# devboard_kw2xd_v2_0.net
KiCad netlist of a schematic drawn in EAGLE
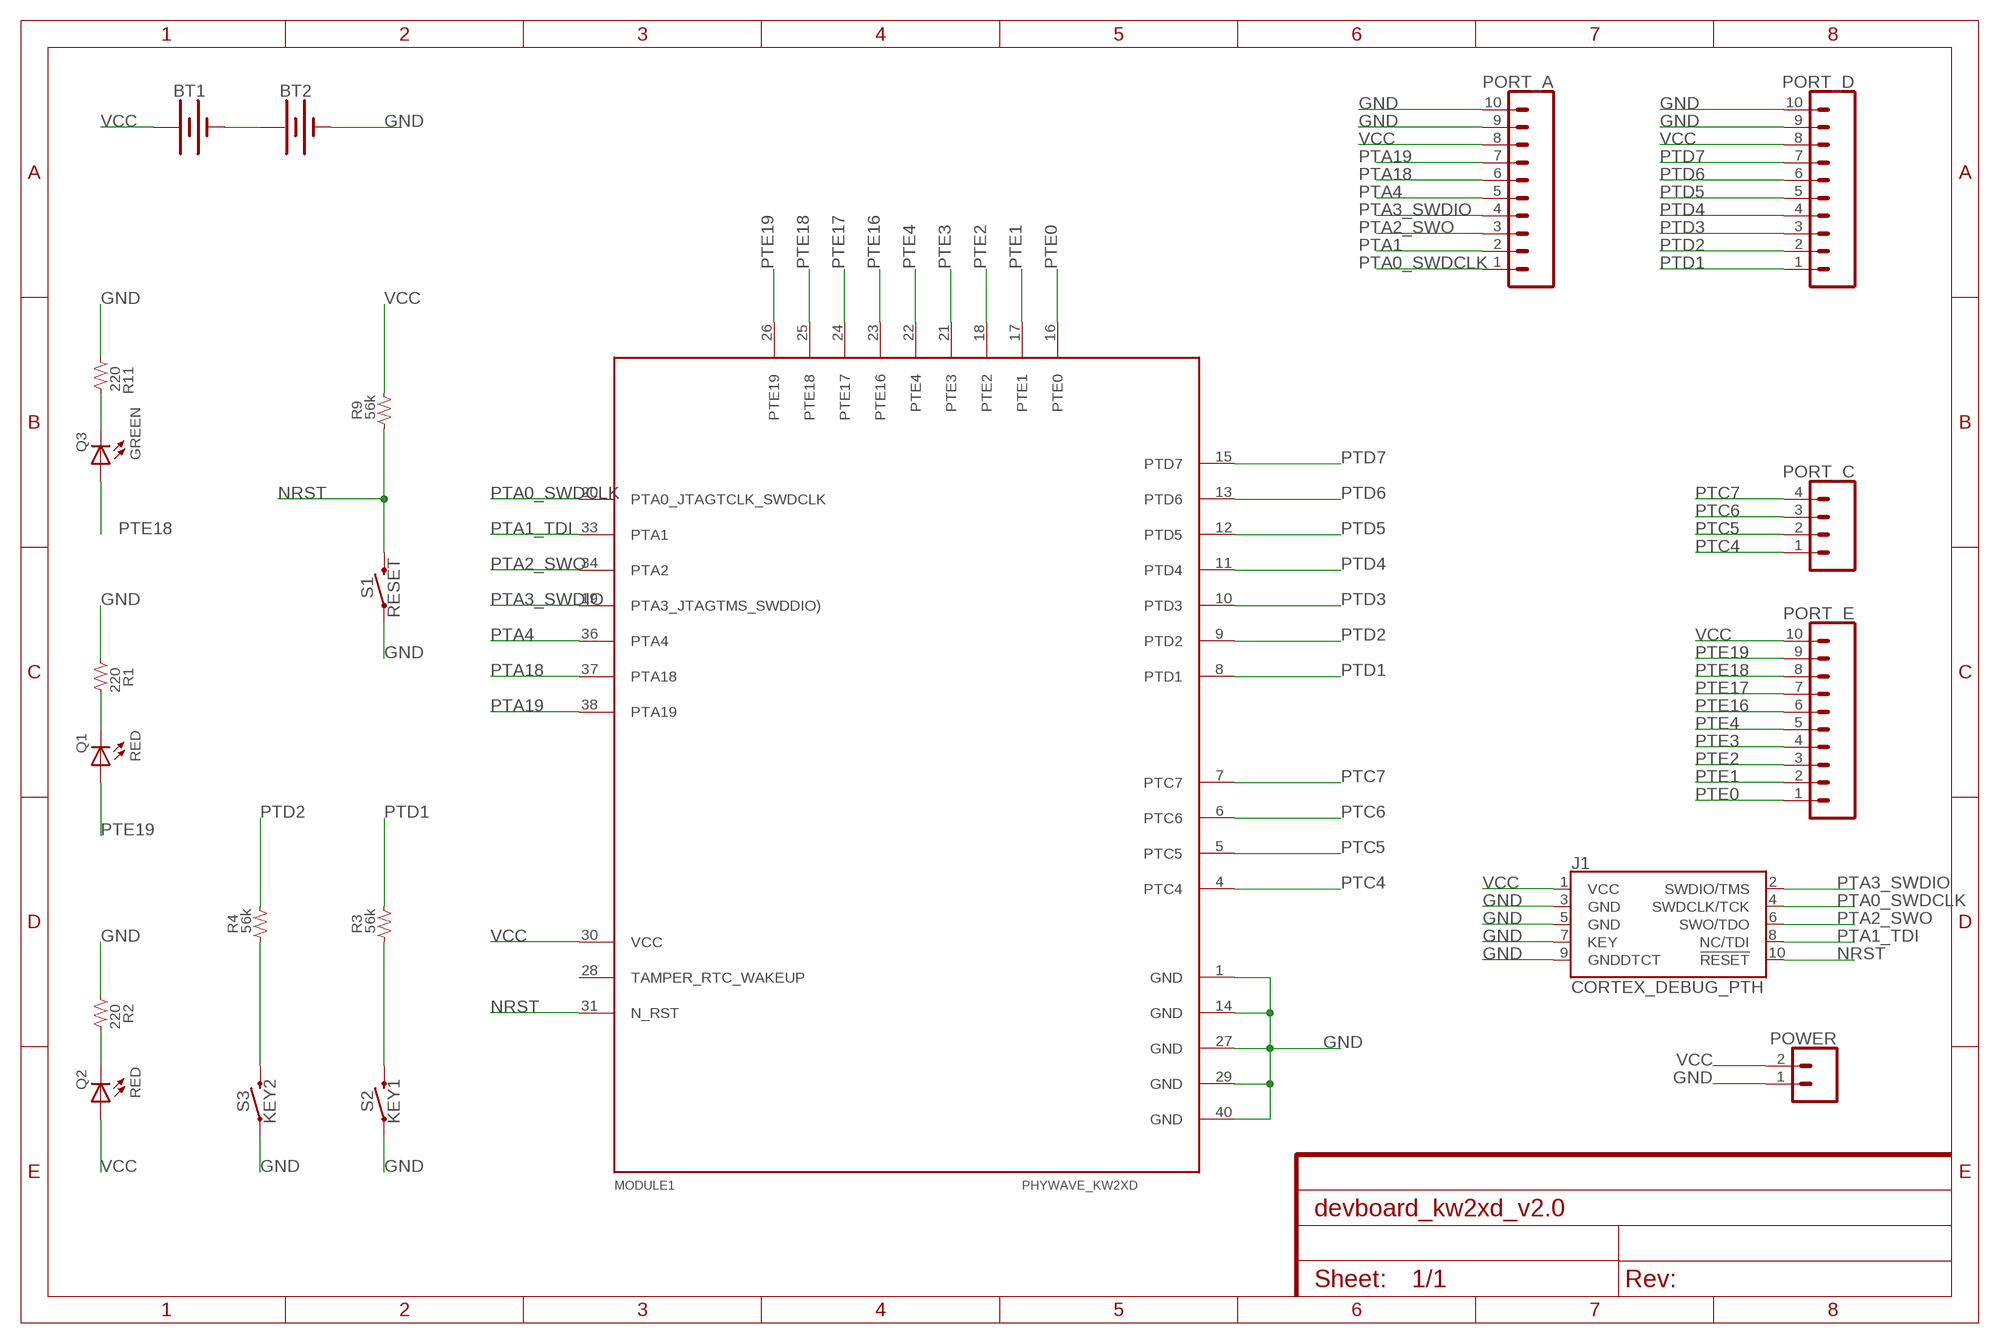
[diagram p0: schematic, sheet 1]

(export (version "E")
  (design (tool "Eeschema 10.0.6"))
  (components
    (comp (ref "BT1")
      (value "BATTERY-AAA")
      (footprint "eagle-import:BATTERY-AAA")
      (libsource (lib "eagle-import") (part "BATTERY-AAA"))
    )
    (comp (ref "BT2")
      (value "BATTERY-AAA")
      (footprint "eagle-import:BATTERY-AAA")
      (libsource (lib "eagle-import") (part "BATTERY-AAA"))
    )
    (comp (ref "J1")
      (value "CORTEX_DEBUG_PTH")
      (footprint "eagle-import:2X5-PTH-1.27MM")
      (libsource (lib "eagle-import") (part "CORTEX_DEBUG_PTH"))
    )
    (comp (ref "MODULE1")
      (value "PHYWAVE_KW2XD")
      (footprint "eagle-import:PHYWAVE_KW2XD")
      (libsource (lib "eagle-import") (part "PHYWAVE_KW2XD"))
    )
    (comp (ref "PORT_A")
      (value "CONN_10\"")
      (footprint "eagle-import:1X10")
      (libsource (lib "eagle-import") (part "CONN_10{dblquote}"))
    )
    (comp (ref "PORT_C")
      (value "CONN_04")
      (footprint "eagle-import:1X04")
      (libsource (lib "eagle-import") (part "CONN_04"))
    )
    (comp (ref "PORT_D")
      (value "CONN_10\"")
      (footprint "eagle-import:1X10")
      (libsource (lib "eagle-import") (part "CONN_10{dblquote}"))
    )
    (comp (ref "PORT_E")
      (value "CONN_10\"")
      (footprint "eagle-import:1X10")
      (libsource (lib "eagle-import") (part "CONN_10{dblquote}"))
    )
    (comp (ref "POWER")
      (value "CONN_02")
      (footprint "eagle-import:1X02")
      (libsource (lib "eagle-import") (part "CONN_02"))
    )
    (comp (ref "Q1")
      (value "RED")
      (footprint "eagle-import:LED0603")
      (libsource (lib "eagle-import") (part "LED-0603"))
    )
    (comp (ref "Q2")
      (value "RED")
      (footprint "eagle-import:LED0603")
      (libsource (lib "eagle-import") (part "LED-0603"))
    )
    (comp (ref "Q3")
      (value "GREEN")
      (footprint "eagle-import:LED0603")
      (libsource (lib "eagle-import") (part "LED-0603"))
    )
    (comp (ref "R1")
      (value "220")
      (footprint "eagle-import:SMD0603")
      (libsource (lib "eagle-import") (part "R-0603"))
    )
    (comp (ref "R2")
      (value "220")
      (footprint "eagle-import:SMD0603")
      (libsource (lib "eagle-import") (part "R-0603"))
    )
    (comp (ref "R3")
      (value "56k")
      (footprint "eagle-import:SMD0603")
      (libsource (lib "eagle-import") (part "R-0603"))
    )
    (comp (ref "R4")
      (value "56k")
      (footprint "eagle-import:SMD0603")
      (libsource (lib "eagle-import") (part "R-0603"))
    )
    (comp (ref "R9")
      (value "56k")
      (footprint "eagle-import:SMD0603")
      (libsource (lib "eagle-import") (part "R-0603"))
    )
    (comp (ref "R11")
      (value "220")
      (footprint "eagle-import:SMD0603")
      (libsource (lib "eagle-import") (part "R-0603"))
    )
    (comp (ref "S1")
      (value "RESET")
      (footprint "eagle-import:TACTILE_SWITCH_SMD_4.6X2.8MM")
      (libsource (lib "eagle-import") (part "MOMENTARY-SWITCH-SPST-SMD-4.6X2.8MM"))
    )
    (comp (ref "S2")
      (value "KEY1")
      (footprint "eagle-import:TACTILE_SWITCH_SMD_4.6X2.8MM")
      (libsource (lib "eagle-import") (part "MOMENTARY-SWITCH-SPST-SMD-4.6X2.8MM"))
    )
    (comp (ref "S3")
      (value "KEY2")
      (footprint "eagle-import:TACTILE_SWITCH_SMD_4.6X2.8MM")
      (libsource (lib "eagle-import") (part "MOMENTARY-SWITCH-SPST-SMD-4.6X2.8MM"))
    )
  )
  (nets
    (net (code "1") (name "/GND") (class "Default")
      (node (ref "BT2") (pin "GND@1") (pinfunction "-_GND@1") (pintype "power_in"))
      (node (ref "J1") (pin "3") (pinfunction "GND_3") (pintype "bidirectional"))
      (node (ref "J1") (pin "5") (pinfunction "GND_5") (pintype "bidirectional"))
      (node (ref "J1") (pin "7") (pinfunction "KEY_7") (pintype "bidirectional"))
      (node (ref "J1") (pin "9") (pinfunction "GNDDTCT_9") (pintype "bidirectional"))
      (node (ref "MODULE1") (pin "1") (pinfunction "GND_1") (pintype "bidirectional"))
      (node (ref "MODULE1") (pin "14") (pinfunction "GND_14") (pintype "bidirectional"))
      (node (ref "MODULE1") (pin "27") (pinfunction "GND_27") (pintype "bidirectional"))
      (node (ref "MODULE1") (pin "29") (pinfunction "GND_29") (pintype "bidirectional"))
      (node (ref "MODULE1") (pin "40") (pinfunction "GND_40") (pintype "bidirectional"))
      (node (ref "PORT_A") (pin "10") (pinfunction "10_10") (pintype "passive"))
      (node (ref "PORT_A") (pin "9") (pinfunction "9_9") (pintype "passive"))
      (node (ref "PORT_D") (pin "10") (pinfunction "10_10") (pintype "passive"))
      (node (ref "PORT_D") (pin "9") (pinfunction "9_9") (pintype "passive"))
      (node (ref "POWER") (pin "1") (pinfunction "1_1") (pintype "passive"))
      (node (ref "R1") (pin "1") (pinfunction "1_1") (pintype "passive"))
      (node (ref "R11") (pin "1") (pinfunction "1_1") (pintype "passive"))
      (node (ref "R2") (pin "1") (pinfunction "1_1") (pintype "passive"))
      (node (ref "S1") (pin "1") (pinfunction "1_1") (pintype "passive"))
      (node (ref "S1") (pin "2") (pinfunction "1_2") (pintype "passive"))
      (node (ref "S2") (pin "1") (pinfunction "1_1") (pintype "passive"))
      (node (ref "S2") (pin "2") (pinfunction "1_2") (pintype "passive"))
      (node (ref "S3") (pin "1") (pinfunction "1_1") (pintype "passive"))
      (node (ref "S3") (pin "2") (pinfunction "1_2") (pintype "passive"))
    )
    (net (code "2") (name "/NRST") (class "Default")
      (node (ref "J1") (pin "10") (pinfunction "~{RESET}_10") (pintype "bidirectional"))
      (node (ref "MODULE1") (pin "31") (pinfunction "N_RST_31") (pintype "bidirectional"))
      (node (ref "R3") (pin "1") (pinfunction "1_1") (pintype "passive"))
      (node (ref "R9") (pin "1") (pinfunction "1_1") (pintype "passive"))
      (node (ref "S1") (pin "3") (pinfunction "2_3") (pintype "passive"))
      (node (ref "S1") (pin "4") (pinfunction "2_4") (pintype "passive"))
      (node (ref "S2") (pin "3") (pinfunction "2_3") (pintype "passive"))
      (node (ref "S2") (pin "4") (pinfunction "2_4") (pintype "passive"))
    )
    (net (code "3") (name "/PTA0_SWDCLK") (class "Default")
      (node (ref "J1") (pin "4") (pinfunction "SWDCLK/TCK_4") (pintype "bidirectional"))
      (node (ref "MODULE1") (pin "20") (pinfunction "PTA0_JTAGTCLK_SWDCLK_20") (pintype "bidirectional"))
      (node (ref "PORT_A") (pin "1") (pinfunction "1_1") (pintype "passive"))
    )
    (net (code "4") (name "/PTA1") (class "Default")
      (node (ref "PORT_A") (pin "2") (pinfunction "2_2") (pintype "passive"))
    )
    (net (code "5") (name "/PTA1_TDI") (class "Default")
      (node (ref "J1") (pin "8") (pinfunction "NC/TDI_8") (pintype "bidirectional"))
      (node (ref "MODULE1") (pin "33") (pinfunction "PTA1_33") (pintype "bidirectional"))
    )
    (net (code "6") (name "/PTA2_SWO") (class "Default")
      (node (ref "J1") (pin "6") (pinfunction "SWO/TDO_6") (pintype "bidirectional"))
      (node (ref "MODULE1") (pin "34") (pinfunction "PTA2_34") (pintype "bidirectional"))
      (node (ref "PORT_A") (pin "3") (pinfunction "3_3") (pintype "passive"))
    )
    (net (code "7") (name "/PTA3_SWDIO") (class "Default")
      (node (ref "J1") (pin "2") (pinfunction "SWDIO/TMS_2") (pintype "bidirectional"))
      (node (ref "MODULE1") (pin "19") (pinfunction "PTA3_JTAGTMS_SWDDIO)_19") (pintype "bidirectional"))
      (node (ref "PORT_A") (pin "4") (pinfunction "4_4") (pintype "passive"))
    )
    (net (code "8") (name "/PTA4") (class "Default")
      (node (ref "MODULE1") (pin "36") (pinfunction "PTA4_36") (pintype "bidirectional"))
      (node (ref "PORT_A") (pin "5") (pinfunction "5_5") (pintype "passive"))
    )
    (net (code "9") (name "/PTA18") (class "Default")
      (node (ref "MODULE1") (pin "37") (pinfunction "PTA18_37") (pintype "bidirectional"))
      (node (ref "PORT_A") (pin "6") (pinfunction "6_6") (pintype "passive"))
    )
    (net (code "10") (name "/PTA19") (class "Default")
      (node (ref "MODULE1") (pin "38") (pinfunction "PTA19_38") (pintype "bidirectional"))
      (node (ref "PORT_A") (pin "7") (pinfunction "7_7") (pintype "passive"))
    )
    (net (code "11") (name "/PTC4") (class "Default")
      (node (ref "MODULE1") (pin "4") (pinfunction "PTC4_4") (pintype "bidirectional"))
      (node (ref "PORT_C") (pin "1") (pinfunction "1_1") (pintype "passive"))
    )
    (net (code "12") (name "/PTC5") (class "Default")
      (node (ref "MODULE1") (pin "5") (pinfunction "PTC5_5") (pintype "bidirectional"))
      (node (ref "PORT_C") (pin "2") (pinfunction "2_2") (pintype "passive"))
    )
    (net (code "13") (name "/PTC6") (class "Default")
      (node (ref "MODULE1") (pin "6") (pinfunction "PTC6_6") (pintype "bidirectional"))
      (node (ref "PORT_C") (pin "3") (pinfunction "3_3") (pintype "passive"))
    )
    (net (code "14") (name "/PTC7") (class "Default")
      (node (ref "MODULE1") (pin "7") (pinfunction "PTC7_7") (pintype "bidirectional"))
      (node (ref "PORT_C") (pin "4") (pinfunction "4_4") (pintype "passive"))
    )
    (net (code "15") (name "/PTD1") (class "Default")
      (node (ref "MODULE1") (pin "8") (pinfunction "PTD1_8") (pintype "bidirectional"))
      (node (ref "PORT_D") (pin "1") (pinfunction "1_1") (pintype "passive"))
      (node (ref "R3") (pin "2") (pinfunction "2_2") (pintype "passive"))
    )
    (net (code "16") (name "/PTD2") (class "Default")
      (node (ref "MODULE1") (pin "9") (pinfunction "PTD2_9") (pintype "bidirectional"))
      (node (ref "PORT_D") (pin "2") (pinfunction "2_2") (pintype "passive"))
      (node (ref "R4") (pin "2") (pinfunction "2_2") (pintype "passive"))
    )
    (net (code "17") (name "/PTD3") (class "Default")
      (node (ref "MODULE1") (pin "10") (pinfunction "PTD3_10") (pintype "bidirectional"))
      (node (ref "PORT_D") (pin "3") (pinfunction "3_3") (pintype "passive"))
    )
    (net (code "18") (name "/PTD4") (class "Default")
      (node (ref "MODULE1") (pin "11") (pinfunction "PTD4_11") (pintype "bidirectional"))
      (node (ref "PORT_D") (pin "4") (pinfunction "4_4") (pintype "passive"))
    )
    (net (code "19") (name "/PTD5") (class "Default")
      (node (ref "MODULE1") (pin "12") (pinfunction "PTD5_12") (pintype "bidirectional"))
      (node (ref "PORT_D") (pin "5") (pinfunction "5_5") (pintype "passive"))
    )
    (net (code "20") (name "/PTD6") (class "Default")
      (node (ref "MODULE1") (pin "13") (pinfunction "PTD6_13") (pintype "bidirectional"))
      (node (ref "PORT_D") (pin "6") (pinfunction "6_6") (pintype "passive"))
    )
    (net (code "21") (name "/PTD7") (class "Default")
      (node (ref "MODULE1") (pin "15") (pinfunction "PTD7_15") (pintype "bidirectional"))
      (node (ref "PORT_D") (pin "7") (pinfunction "7_7") (pintype "passive"))
    )
    (net (code "22") (name "/PTE0") (class "Default")
      (node (ref "MODULE1") (pin "16") (pinfunction "PTE0_16") (pintype "bidirectional"))
      (node (ref "PORT_E") (pin "1") (pinfunction "1_1") (pintype "passive"))
    )
    (net (code "23") (name "/PTE1") (class "Default")
      (node (ref "MODULE1") (pin "17") (pinfunction "PTE1_17") (pintype "bidirectional"))
      (node (ref "PORT_E") (pin "2") (pinfunction "2_2") (pintype "passive"))
    )
    (net (code "24") (name "/PTE2") (class "Default")
      (node (ref "MODULE1") (pin "18") (pinfunction "PTE2_18") (pintype "bidirectional"))
      (node (ref "PORT_E") (pin "3") (pinfunction "3_3") (pintype "passive"))
    )
    (net (code "25") (name "/PTE3") (class "Default")
      (node (ref "MODULE1") (pin "21") (pinfunction "PTE3_21") (pintype "bidirectional"))
      (node (ref "PORT_E") (pin "4") (pinfunction "4_4") (pintype "passive"))
    )
    (net (code "26") (name "/PTE4") (class "Default")
      (node (ref "MODULE1") (pin "22") (pinfunction "PTE4_22") (pintype "bidirectional"))
      (node (ref "PORT_E") (pin "5") (pinfunction "5_5") (pintype "passive"))
    )
    (net (code "27") (name "/PTE16") (class "Default")
      (node (ref "MODULE1") (pin "23") (pinfunction "PTE16_23") (pintype "bidirectional"))
      (node (ref "PORT_E") (pin "6") (pinfunction "6_6") (pintype "passive"))
    )
    (net (code "28") (name "/PTE17") (class "Default")
      (node (ref "MODULE1") (pin "24") (pinfunction "PTE17_24") (pintype "bidirectional"))
      (node (ref "PORT_E") (pin "7") (pinfunction "7_7") (pintype "passive"))
    )
    (net (code "29") (name "/PTE18") (class "Default")
      (node (ref "MODULE1") (pin "25") (pinfunction "PTE18_25") (pintype "bidirectional"))
      (node (ref "PORT_E") (pin "8") (pinfunction "8_8") (pintype "passive"))
      (node (ref "Q3") (pin "A") (pinfunction "A_A") (pintype "passive"))
    )
    (net (code "30") (name "/PTE19") (class "Default")
      (node (ref "MODULE1") (pin "26") (pinfunction "PTE19_26") (pintype "bidirectional"))
      (node (ref "PORT_E") (pin "9") (pinfunction "9_9") (pintype "passive"))
      (node (ref "Q1") (pin "A") (pinfunction "A_A") (pintype "passive"))
    )
    (net (code "31") (name "/VCC") (class "Default")
      (node (ref "BT1") (pin "PWR@1") (pinfunction "+_PWR@1") (pintype "power_in"))
      (node (ref "J1") (pin "1") (pinfunction "VCC_1") (pintype "bidirectional"))
      (node (ref "MODULE1") (pin "30") (pinfunction "VCC_30") (pintype "bidirectional"))
      (node (ref "PORT_A") (pin "8") (pinfunction "8_8") (pintype "passive"))
      (node (ref "PORT_D") (pin "8") (pinfunction "8_8") (pintype "passive"))
      (node (ref "PORT_E") (pin "10") (pinfunction "10_10") (pintype "passive"))
      (node (ref "POWER") (pin "2") (pinfunction "2_2") (pintype "passive"))
      (node (ref "Q2") (pin "A") (pinfunction "A_A") (pintype "passive"))
      (node (ref "R9") (pin "2") (pinfunction "2_2") (pintype "passive"))
    )
    (net (code "32") (name "Net-(BT1--)") (class "Default")
      (node (ref "BT1") (pin "GND@1") (pinfunction "-_GND@1") (pintype "power_in"))
      (node (ref "BT2") (pin "PWR@1") (pinfunction "+_PWR@1") (pintype "power_in"))
    )
    (net (code "33") (name "Net-(Q1-PadC)") (class "Default")
      (node (ref "Q1") (pin "C") (pinfunction "C_C") (pintype "passive"))
      (node (ref "R1") (pin "2") (pinfunction "2_2") (pintype "passive"))
    )
    (net (code "34") (name "Net-(Q2-PadC)") (class "Default")
      (node (ref "Q2") (pin "C") (pinfunction "C_C") (pintype "passive"))
      (node (ref "R2") (pin "2") (pinfunction "2_2") (pintype "passive"))
    )
    (net (code "35") (name "Net-(Q3-PadC)") (class "Default")
      (node (ref "Q3") (pin "C") (pinfunction "C_C") (pintype "passive"))
      (node (ref "R11") (pin "2") (pinfunction "2_2") (pintype "passive"))
    )
    (net (code "36") (name "Net-(R4-Pad1)") (class "Default")
      (node (ref "R4") (pin "1") (pinfunction "1_1") (pintype "passive"))
      (node (ref "S3") (pin "3") (pinfunction "2_3") (pintype "passive"))
      (node (ref "S3") (pin "4") (pinfunction "2_4") (pintype "passive"))
    )
    (net (code "37") (name "unconnected-(MODULE1-TAMPER_RTC_WAKEUP-Pad28)") (class "Default")
      (node (ref "MODULE1") (pin "28") (pinfunction "TAMPER_RTC_WAKEUP_28") (pintype "bidirectional"))
    )
  )
)
